# MB1189.net
KiCad netlist of a schematic drawn in Altium Designer
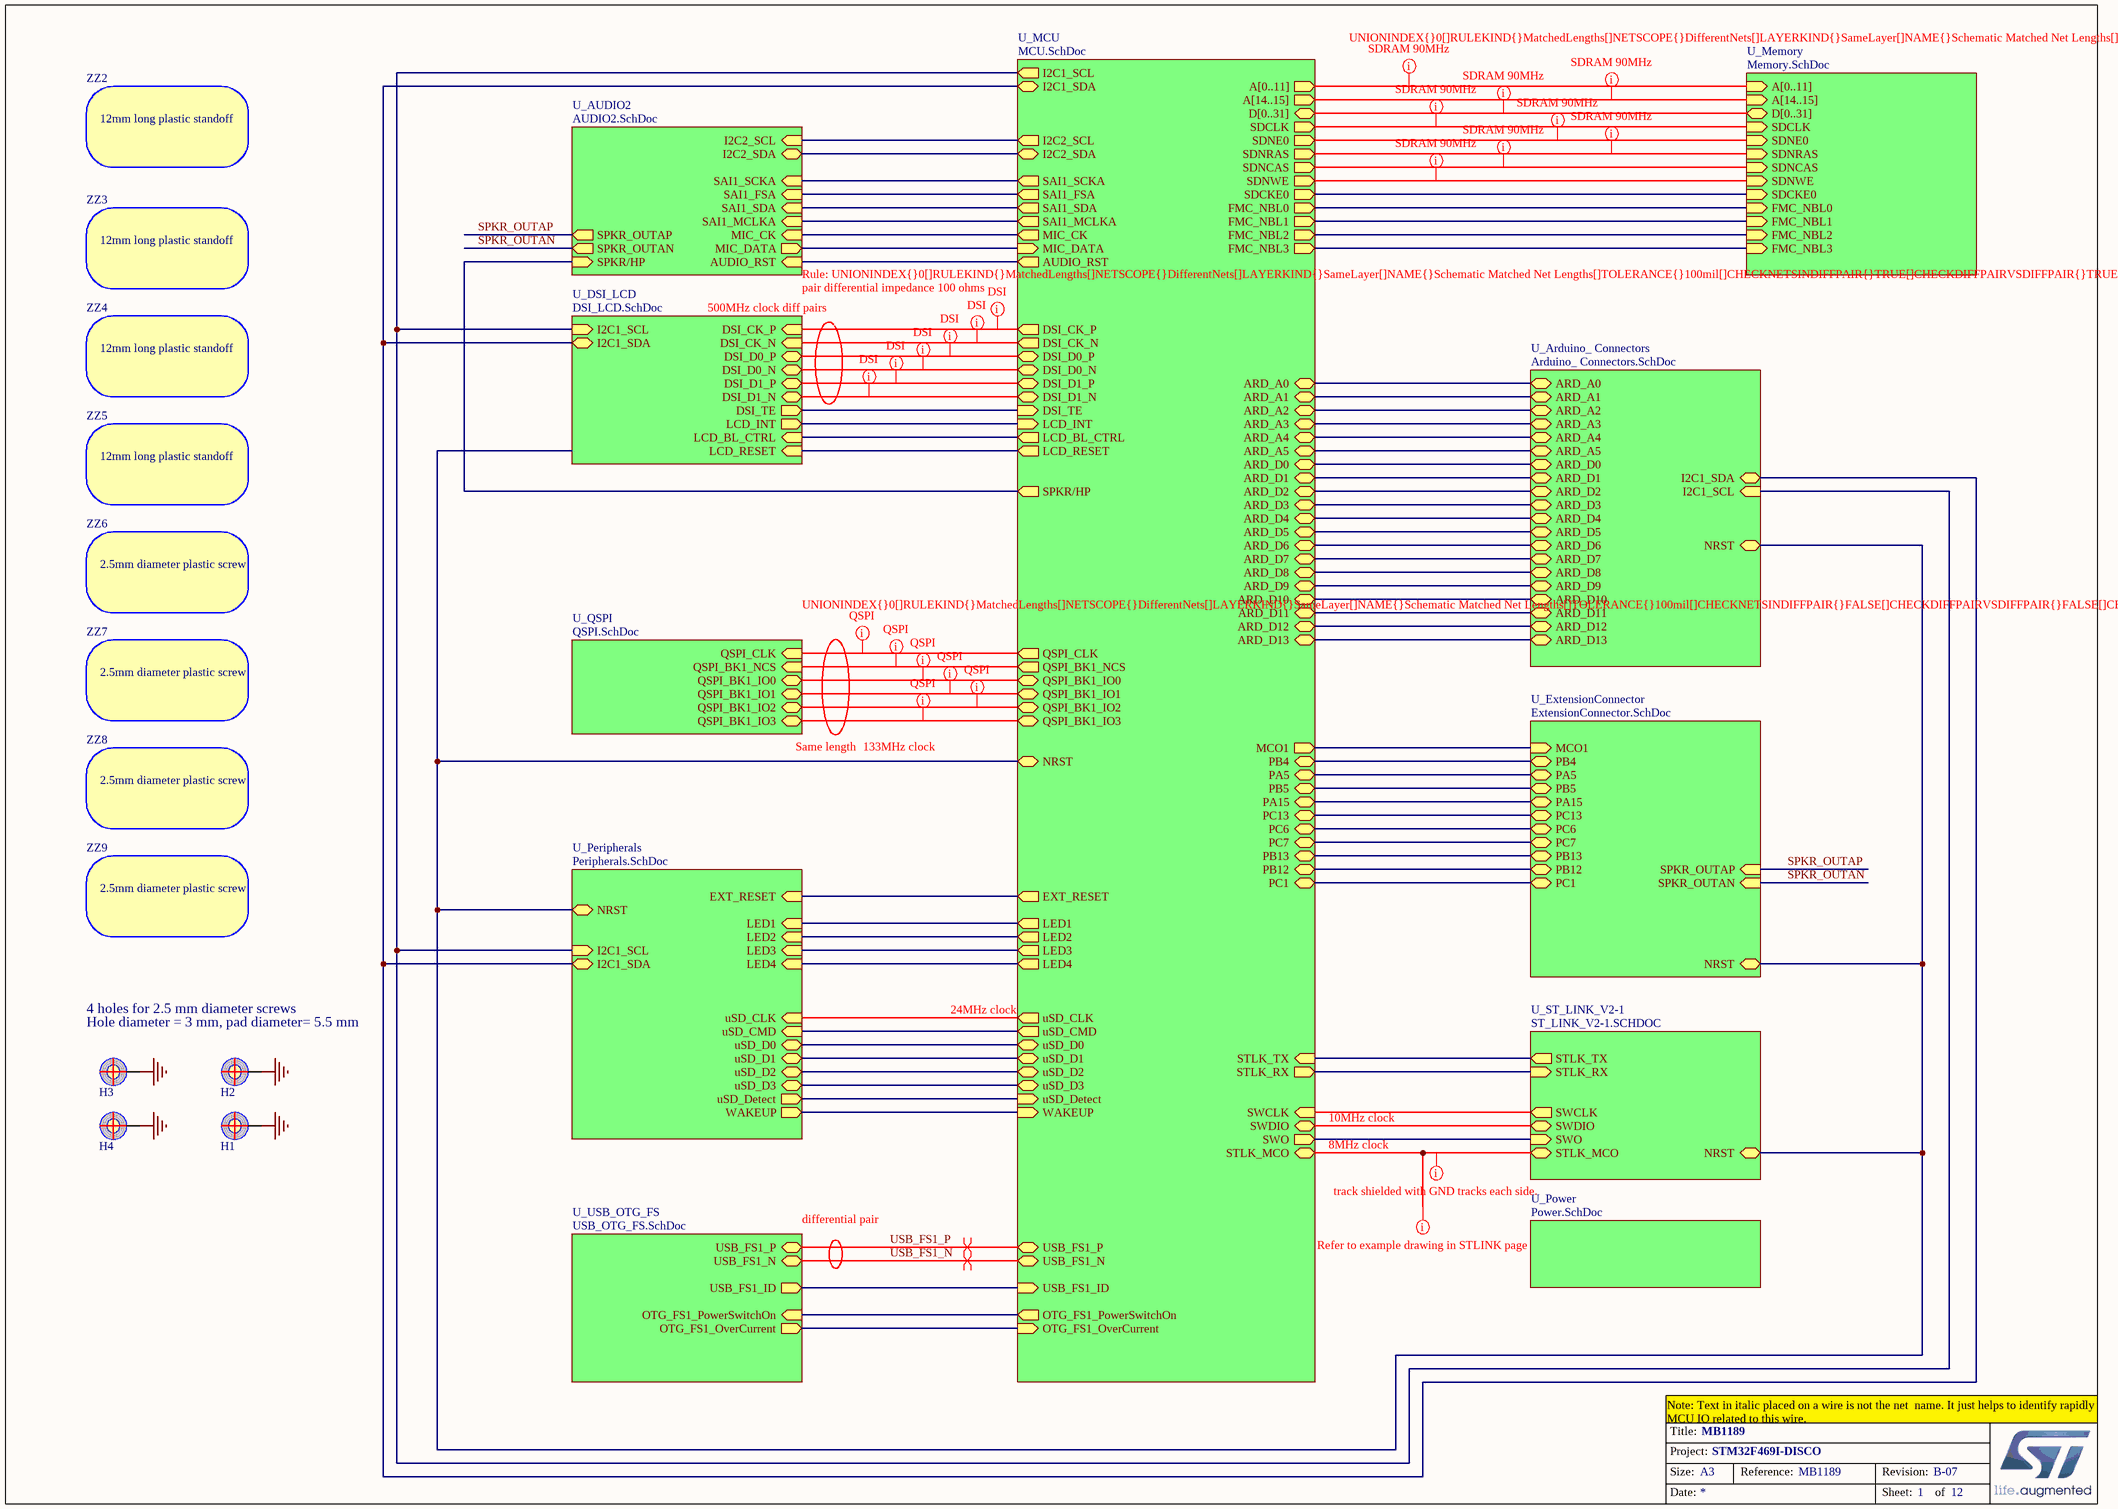
[diagram p0: MB1189.SchDoc]

(export (version "E")
  (design (tool "Eeschema 10.0.6"))
  (components
    (comp (ref "H1")
      (value "POSITION HOLE")
      (footprint "HOLE_C5R5D3")
      (libsource (lib "mb1045") (part "POSITION HOLE"))
    )
    (comp (ref "H2")
      (value "POSITION HOLE")
      (footprint "HOLE_C5R5D3")
      (libsource (lib "mb1045") (part "POSITION HOLE"))
    )
    (comp (ref "H3")
      (value "POSITION HOLE")
      (footprint "HOLE_C5R5D3")
      (libsource (lib "mb1045") (part "POSITION HOLE"))
    )
    (comp (ref "H4")
      (value "POSITION HOLE")
      (footprint "HOLE_C5R5D3")
      (libsource (lib "mb1045") (part "POSITION HOLE"))
    )
    (comp (ref "ZZ2")
      (value "12mm long plastic standoff")
      (description "Heigth Spacer")
      (libsource (lib "Almos") (part "BoM_Item"))
    )
    (comp (ref "ZZ3")
      (value "12mm long plastic standoff")
      (description "Heigth Spacer")
      (libsource (lib "Almos") (part "BoM_Item"))
    )
    (comp (ref "ZZ4")
      (value "12mm long plastic standoff")
      (description "Heigth Spacer")
      (libsource (lib "Almos") (part "BoM_Item"))
    )
    (comp (ref "ZZ5")
      (value "12mm long plastic standoff")
      (description "Heigth Spacer")
      (libsource (lib "Almos") (part "BoM_Item"))
    )
    (comp (ref "ZZ6")
      (value "2.5mm diameter plastic screw")
      (description "Heigth Spacer")
      (libsource (lib "Almos") (part "BoM_Item"))
    )
    (comp (ref "ZZ7")
      (value "2.5mm diameter plastic screw")
      (description "Heigth Spacer")
      (libsource (lib "Almos") (part "BoM_Item"))
    )
    (comp (ref "ZZ8")
      (value "2.5mm diameter plastic screw")
      (description "Heigth Spacer")
      (libsource (lib "Almos") (part "BoM_Item"))
    )
    (comp (ref "ZZ9")
      (value "2.5mm diameter plastic screw")
      (description "Heigth Spacer")
      (libsource (lib "Almos") (part "BoM_Item"))
    )
  )
  (nets
    (net (code "100") (name "GND") (class "Default")
      (node (ref "H1") (pin "1") (pinfunction "1_1") (pintype "passive"))
      (node (ref "H2") (pin "1") (pinfunction "1_1") (pintype "passive"))
      (node (ref "H3") (pin "1") (pinfunction "1_1") (pintype "passive"))
      (node (ref "H4") (pin "1") (pinfunction "1_1") (pintype "passive"))
    )
  )
)
